# main.net
KiCad netlist of a schematic drawn in Altium Designer
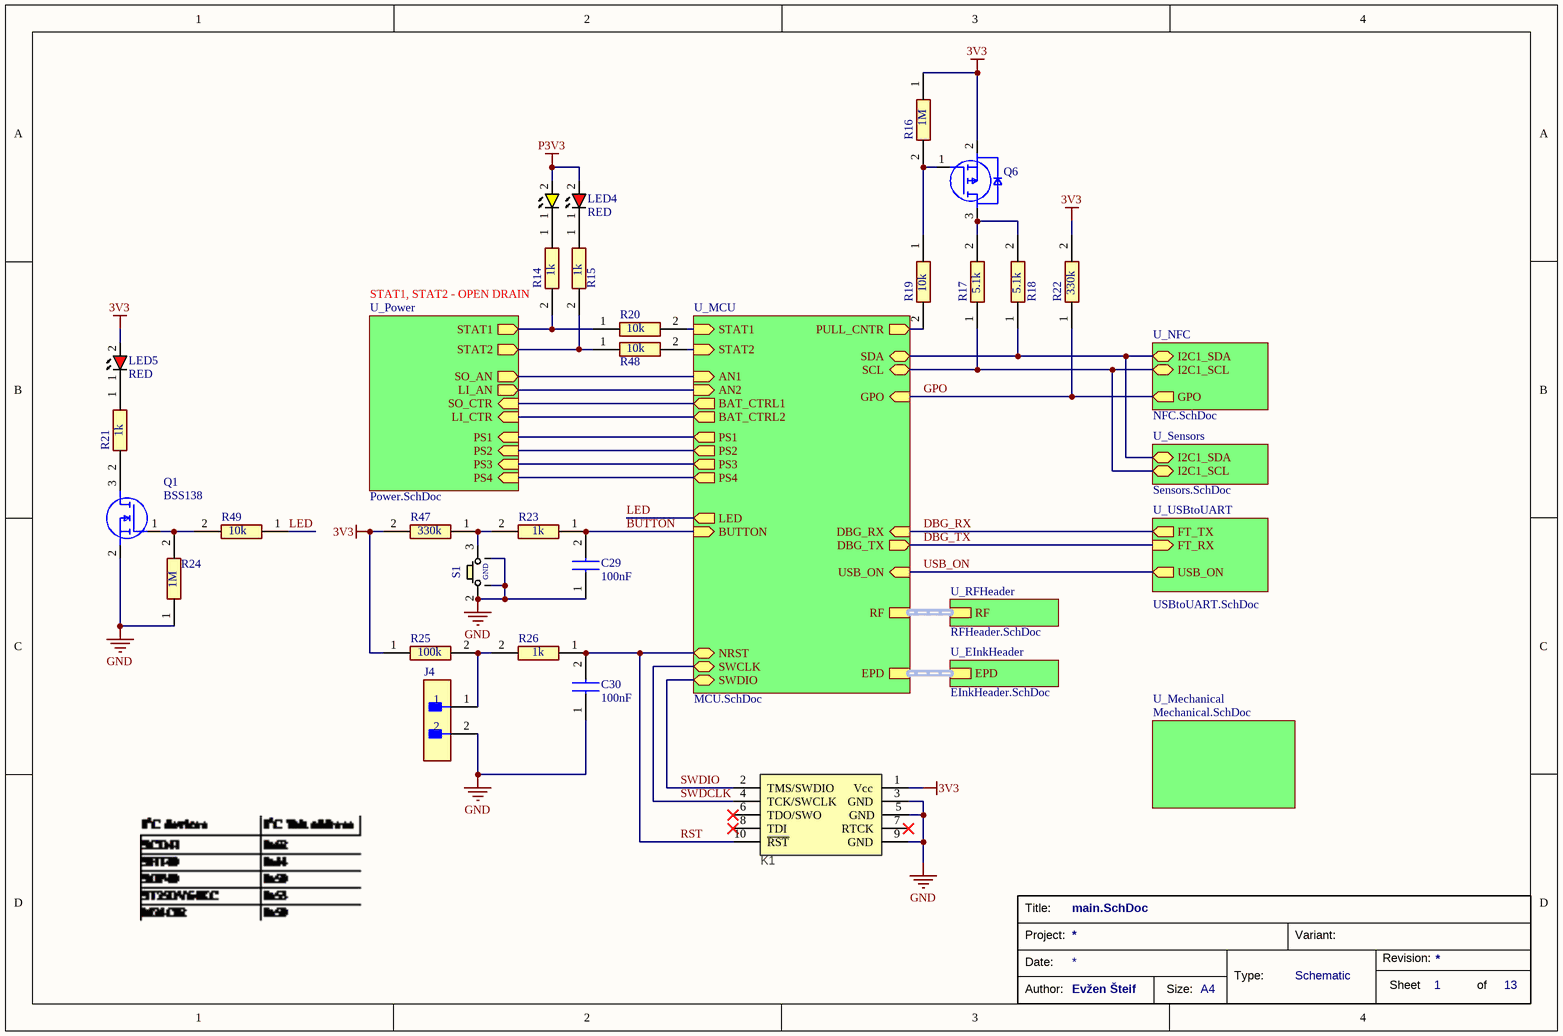
[diagram p0: main.SchDoc]

(export (version "E")
  (design (tool "Eeschema 10.0.6"))
  (components
    (comp (ref "C29")
      (value "100nF")
      (footprint "SamacSys:CAPC1005X70N")
      (description "Capacitor")
      (fields
        (field (name "MANUFACTURER_PART_NUMBER") "GRM155R61A104KA01D")
        (field (name "MOUSER PART NUMBER") "81-GRM155R61A104KA01")
      )
      (libsource (lib "*") (part "GRM155R61A104KA01D"))
    )
    (comp (ref "C30")
      (value "100nF")
      (footprint "SamacSys:CAPC1005X70N")
      (description "Capacitor")
      (fields
        (field (name "MANUFACTURER_PART_NUMBER") "GRM155R61A104KA01D")
        (field (name "MOUSER PART NUMBER") "81-GRM155R61A104KA01")
      )
      (libsource (lib "*") (part "GRM155R61A104KA01D"))
    )
    (comp (ref "J4")
      (value "M20-9990246")
      (footprint "FP-M20-9990246-MFG")
      (description "CONN HEADER VERT 2POS 2.54MM")
      (fields
        (field (name "OCTOPART") "https://octopart.com/m20-9990246-harwin-2590635")
        (field (name "MANUFACTURER") "Harwin")
      )
      (libsource (lib "Altium Content Vault") (part "3bc925449376181038e59eaffc5286c"))
    )
    (comp (ref "K1")
      (value "3220-10-0100-00")
      (footprint "IntLibGenerator:TH_CON_MHDR2X5_PIT50_KEY")
      (description "Cortex ARM JTAG 10 Pin, Header")
      (fields
        (field (name "PARTNUMBER") "TEST_00015")
        (field (name "MANUFACTURER") "CNC Tech")
        (field (name "AUTOR") "Krutina")
        (field (name "DESIGNER") "Krahulec")
        (field (name "LIBRARIAN") "Krahulec")
      )
      (libsource (lib "SamacSys") (part "TEST_00015"))
    )
    (comp (ref "LED3")
      (value "150060YS75000")
      (footprint "SamacSys:LEDC1608X80N")
      (description "LED")
      (fields (field (name "MOUSER PART NUMBER") "710-150060YS75000"))
      (libsource (lib "SamacSys") (part "150060YS75000"))
    )
    (comp (ref "LED4")
      (value "RED")
      (footprint "SamacSys:LEDC1608X80N")
      (description "LED")
      (fields
        (field (name "MANUFACTURER_PART_NUMBER") "150060RS75000")
        (field (name "MOUSER PART NUMBER") "710-150060RS75000")
      )
      (libsource (lib "SamacSys") (part "150060RS55040"))
    )
    (comp (ref "LED5")
      (value "RED")
      (footprint "SamacSys:LEDC1608X80N")
      (description "LED")
      (fields
        (field (name "MANUFACTURER_PART_NUMBER") "150060RS75000")
        (field (name "MOUSER PART NUMBER") "710-150060RS75000")
      )
      (libsource (lib "SamacSys") (part "150060RS55040"))
    )
    (comp (ref "Q1")
      (value "BSS138")
      (footprint "SamacSys:SOT95P240X120-3N")
      (description "MOSFET (N-Channel)")
      (fields (field (name "MOUSER PART NUMBER") "512-BSS138"))
      (libsource (lib "*") (part "BSS138"))
    )
    (comp (ref "Q6")
      (value "SSM3J358R,LF")
      (footprint "SamacSys:SOTFL95P240X88-3N")
      (description "MOSFET (P-Channel)")
      (fields (field (name "MOUSER PART NUMBER") "757-SSM3J358RLF"))
      (libsource (lib "SamacSys") (part "SSM3J358R,LF"))
    )
    (comp (ref "R14")
      (value "1k")
      (footprint "SamacSys:RESC1005X35N")
      (description "Resistor")
      (fields
        (field (name "MANUFACTURER_PART_NUMBER") "RT0402FRE071KL")
        (field (name "ARROW PART NUMBER") "RT0402FRE07100KL")
      )
      (libsource (lib "SamacSys") (part "RT0402FRE071KL"))
    )
    (comp (ref "R15")
      (value "1k")
      (footprint "SamacSys:RESC1005X35N")
      (description "Resistor")
      (fields
        (field (name "MANUFACTURER_PART_NUMBER") "RT0402FRE071KL")
        (field (name "ARROW PART NUMBER") "RT0402FRE07100KL")
      )
      (libsource (lib "SamacSys") (part "RT0402FRE071KL"))
    )
    (comp (ref "R16")
      (value "1M")
      (footprint "SamacSys:RESC1005X40N")
      (description "Resistor")
      (fields
        (field (name "MANUFACTURER_PART_NUMBER") "RC0402FR-071ML")
        (field (name "MOUSER PART NUMBER") "603-RC0402FR-071ML")
      )
      (libsource (lib "") (part "RC0402FR-071ML_1"))
    )
    (comp (ref "R17")
      (value "5.1k")
      (footprint "SamacSys:RESC1005X35N")
      (description "Resistor")
      (fields (field (name "MANUFACTURER_PART_NUMBER") "RT0402FRE075K1L"))
      (libsource (lib "SamacSys") (part "RT0402FRE075K1L"))
    )
    (comp (ref "R18")
      (value "5.1k")
      (footprint "SamacSys:RESC1005X35N")
      (description "Resistor")
      (fields (field (name "MANUFACTURER_PART_NUMBER") "RT0402FRE075K1L"))
      (libsource (lib "SamacSys") (part "RT0402FRE075K1L"))
    )
    (comp (ref "R19")
      (value "10k")
      (footprint "SamacSys:RESC1005X35N")
      (description "Resistor")
      (fields
        (field (name "MANUFACTURER_PART_NUMBER") "RT0402FRE0710KL")
        (field (name "MOUSER PART NUMBER") "603-RT0402FRE0710KL")
      )
      (libsource (lib "SamacSys") (part "RT0402FRE0710KL"))
    )
    (comp (ref "R20")
      (value "10k")
      (footprint "SamacSys:RESC1005X35N")
      (description "Resistor")
      (fields
        (field (name "MANUFACTURER_PART_NUMBER") "RT0402FRE0710KL")
        (field (name "MOUSER PART NUMBER") "603-RT0402FRE0710KL")
      )
      (libsource (lib "") (part "RT0402FRE0710KL_1"))
    )
    (comp (ref "R21")
      (value "1k")
      (footprint "SamacSys:RESC1005X35N")
      (description "Resistor")
      (fields
        (field (name "MANUFACTURER_PART_NUMBER") "RT0402FRE071KL")
        (field (name "ARROW PART NUMBER") "RT0402FRE07100KL")
      )
      (libsource (lib "SamacSys") (part "RT0402FRE071KL"))
    )
    (comp (ref "R22")
      (value "330k")
      (footprint "SamacSys:RESC1005X40N")
      (description "Resistor")
      (fields (field (name "MANUFACTURER_PART_NUMBER") "RC0402BR-07330KL"))
      (libsource (lib "") (part "RC0402BR-07330KL_1"))
    )
    (comp (ref "R23")
      (value "1k")
      (footprint "SamacSys:RESC1005X35N")
      (description "Resistor")
      (fields
        (field (name "MANUFACTURER_PART_NUMBER") "RT0402FRE071KL")
        (field (name "ARROW PART NUMBER") "RT0402FRE07100KL")
      )
      (libsource (lib "") (part "RT0402FRE071KL_1"))
    )
    (comp (ref "R24")
      (value "1M")
      (footprint "SamacSys:RESC1005X40N")
      (description "Resistor")
      (fields
        (field (name "MANUFACTURER_PART_NUMBER") "RC0402FR-071ML")
        (field (name "MOUSER PART NUMBER") "603-RC0402FR-071ML")
      )
      (libsource (lib "*") (part "RC0402FR-071ML"))
    )
    (comp (ref "R25")
      (value "100k")
      (footprint "SamacSys:RESC1005X35N")
      (description "Resistor")
      (fields
        (field (name "MANUFACTURER_PART_NUMBER") "RT0402FRE07100KL")
        (field (name "MOUSER PART NUMBER") "603-RT0402FRE07100KL")
      )
      (libsource (lib "*") (part "RT0402FRE07100KL"))
    )
    (comp (ref "R26")
      (value "1k")
      (footprint "SamacSys:RESC1005X35N")
      (description "Resistor")
      (fields
        (field (name "MANUFACTURER_PART_NUMBER") "RT0402FRE071KL")
        (field (name "ARROW PART NUMBER") "RT0402FRE07100KL")
      )
      (libsource (lib "") (part "RT0402FRE071KL_1"))
    )
    (comp (ref "R47")
      (value "330k")
      (footprint "SamacSys:RESC1005X40N")
      (description "Resistor")
      (fields (field (name "MANUFACTURER_PART_NUMBER") "RC0402BR-07330KL"))
      (libsource (lib "SamacSys") (part "RC0402BR-07330KL"))
    )
    (comp (ref "R48")
      (value "10k")
      (footprint "SamacSys:RESC1005X35N")
      (description "Resistor")
      (fields
        (field (name "MANUFACTURER_PART_NUMBER") "RT0402FRE0710KL")
        (field (name "MOUSER PART NUMBER") "603-RT0402FRE0710KL")
      )
      (libsource (lib "") (part "RT0402FRE0710KL_1"))
    )
    (comp (ref "R49")
      (value "10k")
      (footprint "SamacSys:RESC1005X35N")
      (description "Resistor")
      (fields
        (field (name "MANUFACTURER_PART_NUMBER") "RT0402FRE0710KL")
        (field (name "MOUSER PART NUMBER") "603-RT0402FRE0710KL")
      )
      (libsource (lib "") (part "RT0402FRE0710KL_2"))
    )
    (comp (ref "S1")
      (value "431256038716")
      (footprint "SamacSys:431256038716")
      (description "Switch")
      (fields (field (name "MOUSER PART NUMBER") "710-431256038716"))
      (libsource (lib "SamacSys") (part "431256038716"))
    )
  )
  (nets
    (net (code "3") (name "/BUTTON") (class "Default")
      (node (ref "C29") (pin "2") (pinfunction "2_2") (pintype "passive"))
      (node (ref "R23") (pin "1") (pinfunction "1_1") (pintype "passive"))
    )
    (net (code "7") (name "/GPO") (class "Default")
      (node (ref "R22") (pin "1") (pinfunction "1_1") (pintype "passive"))
    )
    (net (code "8") (name "/I2C1_SCL") (class "Default")
      (node (ref "R17") (pin "1") (pinfunction "1_1") (pintype "passive"))
    )
    (net (code "9") (name "/I2C1_SDA") (class "Default")
      (node (ref "R18") (pin "1") (pinfunction "1_1") (pintype "passive"))
    )
    (net (code "10") (name "/LED") (class "Default")
      (node (ref "R49") (pin "1") (pinfunction "1_1") (pintype "passive"))
    )
    (net (code "16") (name "/PULL_CNTR") (class "Default")
      (node (ref "R19") (pin "2") (pinfunction "2_2") (pintype "passive"))
    )
    (net (code "18") (name "/RST") (class "Default")
      (node (ref "C30") (pin "2") (pinfunction "2_2") (pintype "passive"))
      (node (ref "K1") (pin "10") (pinfunction "~{RST}_10") (pintype "passive"))
      (node (ref "R26") (pin "1") (pinfunction "1_1") (pintype "passive"))
    )
    (net (code "20") (name "/STAT1") (class "Default")
      (node (ref "R14") (pin "2") (pinfunction "2_2") (pintype "passive"))
      (node (ref "R20") (pin "1") (pinfunction "1_1") (pintype "passive"))
    )
    (net (code "21") (name "/STAT1_1") (class "Default")
      (node (ref "R20") (pin "2") (pinfunction "2_2") (pintype "passive"))
    )
    (net (code "22") (name "/STAT2") (class "Default")
      (node (ref "R15") (pin "2") (pinfunction "2_2") (pintype "passive"))
      (node (ref "R48") (pin "1") (pinfunction "1_1") (pintype "passive"))
    )
    (net (code "23") (name "/STAT2_1") (class "Default")
      (node (ref "R48") (pin "2") (pinfunction "2_2") (pintype "passive"))
    )
    (net (code "24") (name "/SWDCLK") (class "Default")
      (node (ref "K1") (pin "4") (pinfunction "TCK/SWCLK_4") (pintype "passive"))
    )
    (net (code "25") (name "/SWDIO") (class "Default")
      (node (ref "K1") (pin "2") (pinfunction "TMS/SWDIO_2") (pintype "passive"))
    )
    (net (code "27") (name "3V3") (class "Default")
      (node (ref "K1") (pin "1") (pinfunction "Vcc_1") (pintype "passive"))
      (node (ref "LED5") (pin "2") (pinfunction "A_2") (pintype "passive"))
      (node (ref "Q6") (pin "2") (pinfunction "S_2") (pintype "passive"))
      (node (ref "R16") (pin "1") (pinfunction "1_1") (pintype "passive"))
      (node (ref "R22") (pin "2") (pinfunction "2_2") (pintype "passive"))
      (node (ref "R25") (pin "1") (pinfunction "1_1") (pintype "passive"))
      (node (ref "R47") (pin "2") (pinfunction "2_2") (pintype "passive"))
    )
    (net (code "28") (name "GND") (class "Default")
      (node (ref "C29") (pin "1") (pinfunction "1_1") (pintype "passive"))
      (node (ref "C30") (pin "1") (pinfunction "1_1") (pintype "passive"))
      (node (ref "J4") (pin "2") (pinfunction "2_2") (pintype "passive"))
      (node (ref "K1") (pin "3") (pinfunction "GND_3") (pintype "passive"))
      (node (ref "K1") (pin "5") (pinfunction "GND_5") (pintype "passive"))
      (node (ref "K1") (pin "9") (pinfunction "GND_9") (pintype "passive"))
      (node (ref "Q1") (pin "2") (pinfunction "S_2") (pintype "passive"))
      (node (ref "R24") (pin "1") (pinfunction "1_1") (pintype "passive"))
      (node (ref "S1") (pin "1") (pinfunction "1_1") (pintype "passive"))
      (node (ref "S1") (pin "2") (pinfunction "2_2") (pintype "passive"))
      (node (ref "S1") (pin "4") (pinfunction "4_4") (pintype "passive"))
    )
    (net (code "29") (name "Net-(J4-Pad1)") (class "Default")
      (node (ref "J4") (pin "1") (pinfunction "1_1") (pintype "passive"))
      (node (ref "R25") (pin "2") (pinfunction "2_2") (pintype "passive"))
      (node (ref "R26") (pin "2") (pinfunction "2_2") (pintype "passive"))
    )
    (net (code "30") (name "Net-(LED3-K)") (class "Default")
      (node (ref "LED3") (pin "1") (pinfunction "K_1") (pintype "passive"))
      (node (ref "R14") (pin "1") (pinfunction "1_1") (pintype "passive"))
    )
    (net (code "31") (name "Net-(LED4-K)") (class "Default")
      (node (ref "LED4") (pin "1") (pinfunction "K_1") (pintype "passive"))
      (node (ref "R15") (pin "1") (pinfunction "1_1") (pintype "passive"))
    )
    (net (code "32") (name "Net-(LED5-K)") (class "Default")
      (node (ref "LED5") (pin "1") (pinfunction "K_1") (pintype "passive"))
      (node (ref "R21") (pin "1") (pinfunction "1_1") (pintype "passive"))
    )
    (net (code "33") (name "Net-(Q1-D)") (class "Default")
      (node (ref "Q1") (pin "3") (pinfunction "D_3") (pintype "passive"))
      (node (ref "R21") (pin "2") (pinfunction "2_2") (pintype "passive"))
    )
    (net (code "34") (name "Net-(Q1-G)") (class "Default")
      (node (ref "Q1") (pin "1") (pinfunction "G_1") (pintype "passive"))
      (node (ref "R24") (pin "2") (pinfunction "2_2") (pintype "passive"))
      (node (ref "R49") (pin "2") (pinfunction "2_2") (pintype "passive"))
    )
    (net (code "35") (name "Net-(Q6-D)") (class "Default")
      (node (ref "Q6") (pin "3") (pinfunction "D_3") (pintype "passive"))
      (node (ref "R17") (pin "2") (pinfunction "2_2") (pintype "passive"))
      (node (ref "R18") (pin "2") (pinfunction "2_2") (pintype "passive"))
    )
    (net (code "36") (name "Net-(Q6-G)") (class "Default")
      (node (ref "Q6") (pin "1") (pinfunction "G_1") (pintype "passive"))
      (node (ref "R16") (pin "2") (pinfunction "2_2") (pintype "passive"))
      (node (ref "R19") (pin "1") (pinfunction "1_1") (pintype "passive"))
    )
    (net (code "37") (name "Net-(R23-Pad2)") (class "Default")
      (node (ref "R23") (pin "2") (pinfunction "2_2") (pintype "passive"))
      (node (ref "R47") (pin "1") (pinfunction "1_1") (pintype "passive"))
      (node (ref "S1") (pin "3") (pinfunction "3_3") (pintype "passive"))
    )
    (net (code "38") (name "P3V3") (class "Default")
      (node (ref "LED3") (pin "2") (pinfunction "A_2") (pintype "passive"))
      (node (ref "LED4") (pin "2") (pinfunction "A_2") (pintype "passive"))
    )
    (net (code "39") (name "unconnected-(K1-RTCK-Pad7)") (class "Default")
      (node (ref "K1") (pin "7") (pinfunction "RTCK_7") (pintype "passive+no_connect"))
    )
    (net (code "40") (name "unconnected-(K1-TDI-Pad8)") (class "Default")
      (node (ref "K1") (pin "8") (pinfunction "TDI_8") (pintype "passive+no_connect"))
    )
    (net (code "41") (name "unconnected-(K1-TDO{slash}SWO-Pad6)") (class "Default")
      (node (ref "K1") (pin "6") (pinfunction "TDO/SWO_6") (pintype "passive+no_connect"))
    )
  )
)
